# PlaybackStylophone.net
KiCad netlist of a schematic drawn in EAGLE
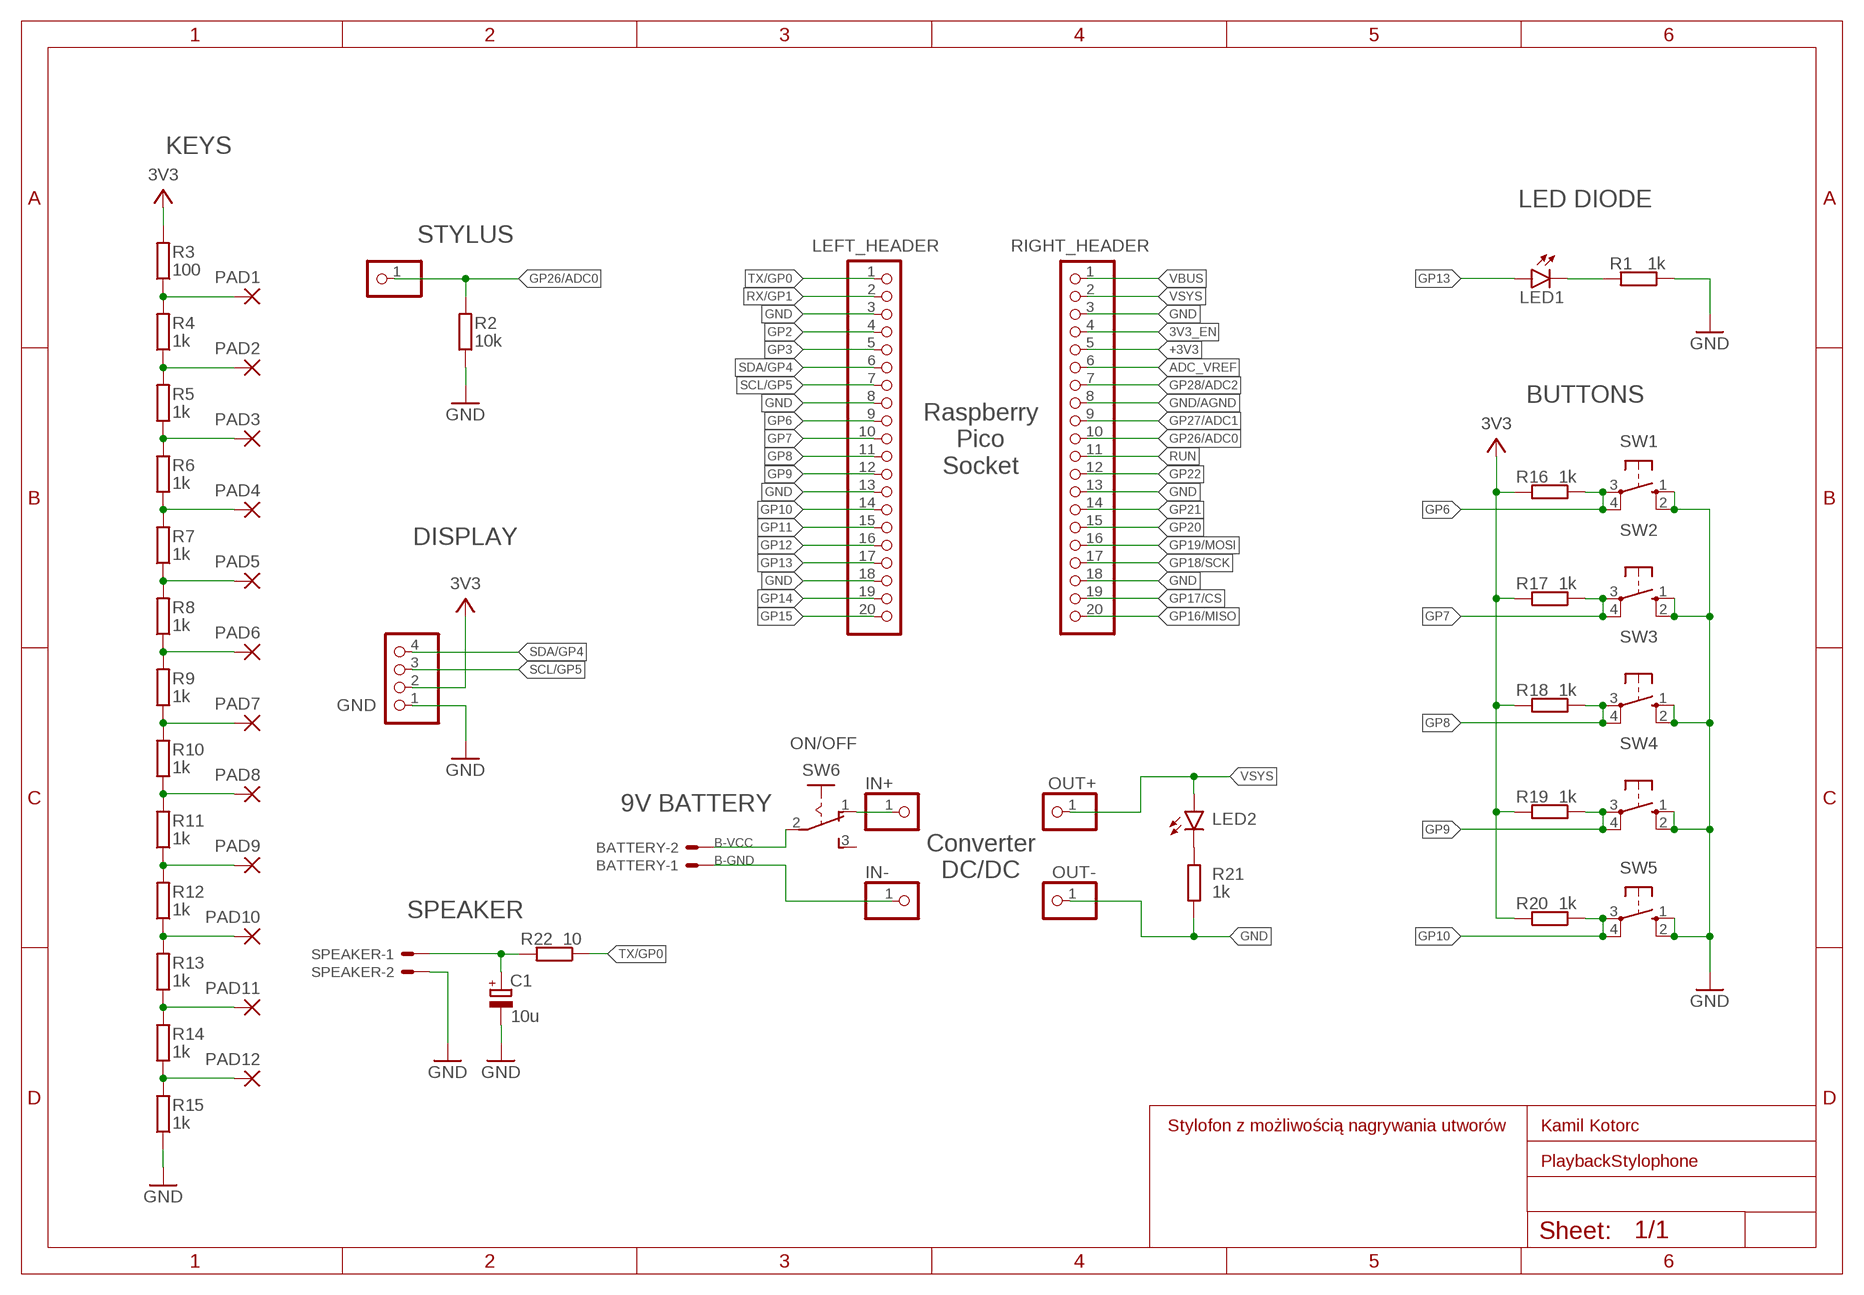
[diagram p0: schematic, sheet 1]

(export (version "E")
  (design (tool "Eeschema 10.0.6"))
  (components
    (comp (ref "BATTERY")
      (value "9V BATTERY")
      (footprint "eagle-import:22-23-2021")
      (fields (field (name "MF") "MOLEX") (field (name "MPN") "22-23-2021"))
      (libsource (lib "eagle-import") (part "22-23-2021"))
    )
    (comp (ref "C1")
      (value "10u")
      (footprint "eagle-import:E2,5-5")
      (libsource (lib "eagle-import") (part "CPOL-EUE2.5-5"))
    )
    (comp (ref "DISPLAY")
      (value "GND")
      (footprint "eagle-import:1X04")
      (libsource (lib "eagle-import") (part "PINHD-1X4"))
    )
    (comp (ref "IN+")
      (value "PINHD-1X1")
      (footprint "eagle-import:1X01")
      (libsource (lib "eagle-import") (part "PINHD-1X1"))
    )
    (comp (ref "IN-")
      (value "PINHD-1X1")
      (footprint "eagle-import:1X01")
      (libsource (lib "eagle-import") (part "PINHD-1X1"))
    )
    (comp (ref "LED1")
      (value "LED5MM")
      (footprint "eagle-import:LED5MM")
      (libsource (lib "eagle-import") (part "LED5MM"))
    )
    (comp (ref "LED2")
      (value "LED3MM")
      (footprint "eagle-import:LED3MM")
      (libsource (lib "eagle-import") (part "LED3MM"))
    )
    (comp (ref "LEFT_HEADER")
      (value "PINHD-1X20")
      (footprint "eagle-import:1X20")
      (libsource (lib "eagle-import") (part "PINHD-1X20"))
    )
    (comp (ref "OUT+")
      (value "PINHD-1X1")
      (footprint "eagle-import:1X01")
      (libsource (lib "eagle-import") (part "PINHD-1X1"))
    )
    (comp (ref "OUT-")
      (value "PINHD-1X1")
      (footprint "eagle-import:1X01")
      (libsource (lib "eagle-import") (part "PINHD-1X1"))
    )
    (comp (ref "PAD1")
      (value "SMD5")
      (footprint "eagle-import:SMD2,54-5,08")
      (libsource (lib "eagle-import") (part "SMD5"))
    )
    (comp (ref "PAD2")
      (value "SMD5")
      (footprint "eagle-import:SMD2,54-5,08")
      (libsource (lib "eagle-import") (part "SMD5"))
    )
    (comp (ref "PAD3")
      (value "SMD5")
      (footprint "eagle-import:SMD2,54-5,08")
      (libsource (lib "eagle-import") (part "SMD5"))
    )
    (comp (ref "PAD4")
      (value "SMD5")
      (footprint "eagle-import:SMD2,54-5,08")
      (libsource (lib "eagle-import") (part "SMD5"))
    )
    (comp (ref "PAD5")
      (value "SMD5")
      (footprint "eagle-import:SMD2,54-5,08")
      (libsource (lib "eagle-import") (part "SMD5"))
    )
    (comp (ref "PAD6")
      (value "SMD5")
      (footprint "eagle-import:SMD2,54-5,08")
      (libsource (lib "eagle-import") (part "SMD5"))
    )
    (comp (ref "PAD7")
      (value "SMD5")
      (footprint "eagle-import:SMD2,54-5,08")
      (libsource (lib "eagle-import") (part "SMD5"))
    )
    (comp (ref "PAD8")
      (value "SMD5")
      (footprint "eagle-import:SMD2,54-5,08")
      (libsource (lib "eagle-import") (part "SMD5"))
    )
    (comp (ref "PAD9")
      (value "SMD5")
      (footprint "eagle-import:SMD2,54-5,08")
      (libsource (lib "eagle-import") (part "SMD5"))
    )
    (comp (ref "PAD10")
      (value "SMD5")
      (footprint "eagle-import:SMD2,54-5,08")
      (libsource (lib "eagle-import") (part "SMD5"))
    )
    (comp (ref "PAD11")
      (value "SMD5")
      (footprint "eagle-import:SMD2,54-5,08")
      (libsource (lib "eagle-import") (part "SMD5"))
    )
    (comp (ref "PAD12")
      (value "SMD5")
      (footprint "eagle-import:SMD2,54-5,08")
      (libsource (lib "eagle-import") (part "SMD5"))
    )
    (comp (ref "R1")
      (value "1k")
      (footprint "eagle-import:0204_7")
      (libsource (lib "eagle-import") (part "R-EU_0204/7"))
    )
    (comp (ref "R2")
      (value "10k")
      (footprint "eagle-import:0204_7")
      (libsource (lib "eagle-import") (part "R-EU_0204/7"))
    )
    (comp (ref "R3")
      (value "100")
      (footprint "eagle-import:0204_7")
      (libsource (lib "eagle-import") (part "R-EU_0204/7"))
    )
    (comp (ref "R4")
      (value "1k")
      (footprint "eagle-import:0204_7")
      (libsource (lib "eagle-import") (part "R-EU_0204/7"))
    )
    (comp (ref "R5")
      (value "1k")
      (footprint "eagle-import:0204_7")
      (libsource (lib "eagle-import") (part "R-EU_0204/7"))
    )
    (comp (ref "R6")
      (value "1k")
      (footprint "eagle-import:0204_7")
      (libsource (lib "eagle-import") (part "R-EU_0204/7"))
    )
    (comp (ref "R7")
      (value "1k")
      (footprint "eagle-import:0204_7")
      (libsource (lib "eagle-import") (part "R-EU_0204/7"))
    )
    (comp (ref "R8")
      (value "1k")
      (footprint "eagle-import:0204_7")
      (libsource (lib "eagle-import") (part "R-EU_0204/7"))
    )
    (comp (ref "R9")
      (value "1k")
      (footprint "eagle-import:0204_7")
      (libsource (lib "eagle-import") (part "R-EU_0204/7"))
    )
    (comp (ref "R10")
      (value "1k")
      (footprint "eagle-import:0204_7")
      (libsource (lib "eagle-import") (part "R-EU_0204/7"))
    )
    (comp (ref "R11")
      (value "1k")
      (footprint "eagle-import:0204_7")
      (libsource (lib "eagle-import") (part "R-EU_0204/7"))
    )
    (comp (ref "R12")
      (value "1k")
      (footprint "eagle-import:0204_7")
      (libsource (lib "eagle-import") (part "R-EU_0204/7"))
    )
    (comp (ref "R13")
      (value "1k")
      (footprint "eagle-import:0204_7")
      (libsource (lib "eagle-import") (part "R-EU_0204/7"))
    )
    (comp (ref "R14")
      (value "1k")
      (footprint "eagle-import:0204_7")
      (libsource (lib "eagle-import") (part "R-EU_0204/7"))
    )
    (comp (ref "R15")
      (value "1k")
      (footprint "eagle-import:0204_7")
      (libsource (lib "eagle-import") (part "R-EU_0204/7"))
    )
    (comp (ref "R16")
      (value "1k")
      (footprint "eagle-import:0204_7")
      (libsource (lib "eagle-import") (part "R-EU_0204/7"))
    )
    (comp (ref "R17")
      (value "1k")
      (footprint "eagle-import:0204_7")
      (libsource (lib "eagle-import") (part "R-EU_0204/7"))
    )
    (comp (ref "R18")
      (value "1k")
      (footprint "eagle-import:0204_7")
      (libsource (lib "eagle-import") (part "R-EU_0204/7"))
    )
    (comp (ref "R19")
      (value "1k")
      (footprint "eagle-import:0204_7")
      (libsource (lib "eagle-import") (part "R-EU_0204/7"))
    )
    (comp (ref "R20")
      (value "1k")
      (footprint "eagle-import:0204_7")
      (libsource (lib "eagle-import") (part "R-EU_0204/7"))
    )
    (comp (ref "R21")
      (value "1k")
      (footprint "eagle-import:0204_7")
      (libsource (lib "eagle-import") (part "R-EU_0204/7"))
    )
    (comp (ref "R22")
      (value "10")
      (footprint "eagle-import:0204_7")
      (libsource (lib "eagle-import") (part "R-EU_0204/7"))
    )
    (comp (ref "RIGHT_HEADER")
      (value "PINHD-1X20")
      (footprint "eagle-import:1X20")
      (libsource (lib "eagle-import") (part "PINHD-1X20"))
    )
    (comp (ref "SPEAKER")
      (value "SPEAKER")
      (footprint "eagle-import:22-23-2021")
      (fields (field (name "MF") "MOLEX") (field (name "MPN") "22-23-2021"))
      (libsource (lib "eagle-import") (part "22-23-2021"))
    )
    (comp (ref "STYLUS")
      (value "PINHD-1X1")
      (footprint "eagle-import:1X01")
      (libsource (lib "eagle-import") (part "PINHD-1X1"))
    )
    (comp (ref "SW1")
      (value "10-XX")
      (footprint "eagle-import:B3F-10XX")
      (fields (field (name "MPN") "B3F-1000"))
      (libsource (lib "eagle-import") (part "10-XX"))
    )
    (comp (ref "SW2")
      (value "10-XX")
      (footprint "eagle-import:B3F-10XX")
      (fields (field (name "MPN") "B3F-1000"))
      (libsource (lib "eagle-import") (part "10-XX"))
    )
    (comp (ref "SW3")
      (value "10-XX")
      (footprint "eagle-import:B3F-10XX")
      (fields (field (name "MPN") "B3F-1000"))
      (libsource (lib "eagle-import") (part "10-XX"))
    )
    (comp (ref "SW4")
      (value "10-XX")
      (footprint "eagle-import:B3F-10XX")
      (fields (field (name "MPN") "B3F-1000"))
      (libsource (lib "eagle-import") (part "10-XX"))
    )
    (comp (ref "SW5")
      (value "10-XX")
      (footprint "eagle-import:B3F-10XX")
      (fields (field (name "MPN") "B3F-1000"))
      (libsource (lib "eagle-import") (part "10-XX"))
    )
    (comp (ref "SW6")
      (value "ON/OFF")
      (footprint "eagle-import:255SB")
      (libsource (lib "eagle-import") (part "255SB"))
    )
  )
  (nets
    (net (code "1") (name "+3V3") (class "Default")
      (node (ref "DISPLAY") (pin "2") (pinfunction "2_2") (pintype "passive"))
      (node (ref "R16") (pin "2") (pinfunction "2_2") (pintype "passive"))
      (node (ref "R17") (pin "2") (pinfunction "2_2") (pintype "passive"))
      (node (ref "R18") (pin "2") (pinfunction "2_2") (pintype "passive"))
      (node (ref "R19") (pin "2") (pinfunction "2_2") (pintype "passive"))
      (node (ref "R20") (pin "2") (pinfunction "2_2") (pintype "passive"))
      (node (ref "R3") (pin "2") (pinfunction "2_2") (pintype "passive"))
      (node (ref "RIGHT_HEADER") (pin "5") (pinfunction "5_5") (pintype "passive"))
    )
    (net (code "2") (name "/B-GND") (class "Default")
      (node (ref "BATTERY") (pin "1") (pinfunction "S_1") (pintype "passive"))
      (node (ref "IN-") (pin "1") (pinfunction "1_1") (pintype "passive"))
    )
    (net (code "3") (name "/B-VCC") (class "Default")
      (node (ref "BATTERY") (pin "2") (pinfunction "S_2") (pintype "passive"))
      (node (ref "SW6") (pin "2") (pinfunction "P_2") (pintype "passive"))
    )
    (net (code "4") (name "3V3_EN") (class "Default")
      (node (ref "RIGHT_HEADER") (pin "4") (pinfunction "4_4") (pintype "passive"))
    )
    (net (code "5") (name "ADC_VREF") (class "Default")
      (node (ref "RIGHT_HEADER") (pin "6") (pinfunction "6_6") (pintype "passive"))
    )
    (net (code "6") (name "GND") (class "Default")
      (node (ref "C1") (pin "-") (pinfunction "-_-") (pintype "passive"))
      (node (ref "DISPLAY") (pin "1") (pinfunction "1_1") (pintype "passive"))
      (node (ref "LEFT_HEADER") (pin "13") (pinfunction "13_13") (pintype "passive"))
      (node (ref "LEFT_HEADER") (pin "18") (pinfunction "18_18") (pintype "passive"))
      (node (ref "LEFT_HEADER") (pin "3") (pinfunction "3_3") (pintype "passive"))
      (node (ref "LEFT_HEADER") (pin "8") (pinfunction "8_8") (pintype "passive"))
      (node (ref "OUT-") (pin "1") (pinfunction "1_1") (pintype "passive"))
      (node (ref "R1") (pin "1") (pinfunction "1_1") (pintype "passive"))
      (node (ref "R15") (pin "1") (pinfunction "1_1") (pintype "passive"))
      (node (ref "R2") (pin "1") (pinfunction "1_1") (pintype "passive"))
      (node (ref "R21") (pin "1") (pinfunction "1_1") (pintype "passive"))
      (node (ref "RIGHT_HEADER") (pin "13") (pinfunction "13_13") (pintype "passive"))
      (node (ref "RIGHT_HEADER") (pin "18") (pinfunction "18_18") (pintype "passive"))
      (node (ref "RIGHT_HEADER") (pin "3") (pinfunction "3_3") (pintype "passive"))
      (node (ref "SPEAKER") (pin "2") (pinfunction "S_2") (pintype "passive"))
      (node (ref "SW1") (pin "1") (pinfunction "S_1") (pintype "passive"))
      (node (ref "SW1") (pin "2") (pinfunction "S1_2") (pintype "passive"))
      (node (ref "SW2") (pin "1") (pinfunction "S_1") (pintype "passive"))
      (node (ref "SW2") (pin "2") (pinfunction "S1_2") (pintype "passive"))
      (node (ref "SW3") (pin "1") (pinfunction "S_1") (pintype "passive"))
      (node (ref "SW3") (pin "2") (pinfunction "S1_2") (pintype "passive"))
      (node (ref "SW4") (pin "1") (pinfunction "S_1") (pintype "passive"))
      (node (ref "SW4") (pin "2") (pinfunction "S1_2") (pintype "passive"))
      (node (ref "SW5") (pin "1") (pinfunction "S_1") (pintype "passive"))
      (node (ref "SW5") (pin "2") (pinfunction "S1_2") (pintype "passive"))
    )
    (net (code "7") (name "GND{slash}AGND") (class "Default")
      (node (ref "RIGHT_HEADER") (pin "8") (pinfunction "8_8") (pintype "passive"))
    )
    (net (code "8") (name "GP2") (class "Default")
      (node (ref "LEFT_HEADER") (pin "4") (pinfunction "4_4") (pintype "passive"))
    )
    (net (code "9") (name "GP3") (class "Default")
      (node (ref "LEFT_HEADER") (pin "5") (pinfunction "5_5") (pintype "passive"))
    )
    (net (code "10") (name "GP6") (class "Default")
      (node (ref "LEFT_HEADER") (pin "9") (pinfunction "9_9") (pintype "passive"))
      (node (ref "R16") (pin "1") (pinfunction "1_1") (pintype "passive"))
      (node (ref "SW1") (pin "3") (pinfunction "P_3") (pintype "passive"))
      (node (ref "SW1") (pin "4") (pinfunction "P1_4") (pintype "passive"))
    )
    (net (code "11") (name "GP7") (class "Default")
      (node (ref "LEFT_HEADER") (pin "10") (pinfunction "10_10") (pintype "passive"))
      (node (ref "R17") (pin "1") (pinfunction "1_1") (pintype "passive"))
      (node (ref "SW2") (pin "3") (pinfunction "P_3") (pintype "passive"))
      (node (ref "SW2") (pin "4") (pinfunction "P1_4") (pintype "passive"))
    )
    (net (code "12") (name "GP8") (class "Default")
      (node (ref "LEFT_HEADER") (pin "11") (pinfunction "11_11") (pintype "passive"))
      (node (ref "R18") (pin "1") (pinfunction "1_1") (pintype "passive"))
      (node (ref "SW3") (pin "3") (pinfunction "P_3") (pintype "passive"))
      (node (ref "SW3") (pin "4") (pinfunction "P1_4") (pintype "passive"))
    )
    (net (code "13") (name "GP9") (class "Default")
      (node (ref "LEFT_HEADER") (pin "12") (pinfunction "12_12") (pintype "passive"))
      (node (ref "R19") (pin "1") (pinfunction "1_1") (pintype "passive"))
      (node (ref "SW4") (pin "3") (pinfunction "P_3") (pintype "passive"))
      (node (ref "SW4") (pin "4") (pinfunction "P1_4") (pintype "passive"))
    )
    (net (code "14") (name "GP10") (class "Default")
      (node (ref "LEFT_HEADER") (pin "14") (pinfunction "14_14") (pintype "passive"))
      (node (ref "R20") (pin "1") (pinfunction "1_1") (pintype "passive"))
      (node (ref "SW5") (pin "3") (pinfunction "P_3") (pintype "passive"))
      (node (ref "SW5") (pin "4") (pinfunction "P1_4") (pintype "passive"))
    )
    (net (code "15") (name "GP11") (class "Default")
      (node (ref "LEFT_HEADER") (pin "15") (pinfunction "15_15") (pintype "passive"))
    )
    (net (code "16") (name "GP12") (class "Default")
      (node (ref "LEFT_HEADER") (pin "16") (pinfunction "16_16") (pintype "passive"))
    )
    (net (code "17") (name "GP13") (class "Default")
      (node (ref "LED1") (pin "A") (pinfunction "A_A") (pintype "passive"))
      (node (ref "LEFT_HEADER") (pin "17") (pinfunction "17_17") (pintype "passive"))
    )
    (net (code "18") (name "GP14") (class "Default")
      (node (ref "LEFT_HEADER") (pin "19") (pinfunction "19_19") (pintype "passive"))
    )
    (net (code "19") (name "GP15") (class "Default")
      (node (ref "LEFT_HEADER") (pin "20") (pinfunction "20_20") (pintype "passive"))
    )
    (net (code "20") (name "GP16{slash}MISO") (class "Default")
      (node (ref "RIGHT_HEADER") (pin "20") (pinfunction "20_20") (pintype "passive"))
    )
    (net (code "21") (name "GP17{slash}CS") (class "Default")
      (node (ref "RIGHT_HEADER") (pin "19") (pinfunction "19_19") (pintype "passive"))
    )
    (net (code "22") (name "GP18{slash}SCK") (class "Default")
      (node (ref "RIGHT_HEADER") (pin "17") (pinfunction "17_17") (pintype "passive"))
    )
    (net (code "23") (name "GP19{slash}MOSI") (class "Default")
      (node (ref "RIGHT_HEADER") (pin "16") (pinfunction "16_16") (pintype "passive"))
    )
    (net (code "24") (name "GP20") (class "Default")
      (node (ref "RIGHT_HEADER") (pin "15") (pinfunction "15_15") (pintype "passive"))
    )
    (net (code "25") (name "GP21") (class "Default")
      (node (ref "RIGHT_HEADER") (pin "14") (pinfunction "14_14") (pintype "passive"))
    )
    (net (code "26") (name "GP22") (class "Default")
      (node (ref "RIGHT_HEADER") (pin "12") (pinfunction "12_12") (pintype "passive"))
    )
    (net (code "27") (name "GP26{slash}ADC0") (class "Default")
      (node (ref "R2") (pin "2") (pinfunction "2_2") (pintype "passive"))
      (node (ref "RIGHT_HEADER") (pin "10") (pinfunction "10_10") (pintype "passive"))
      (node (ref "STYLUS") (pin "1") (pinfunction "1_1") (pintype "passive"))
    )
    (net (code "28") (name "GP27{slash}ADC1") (class "Default")
      (node (ref "RIGHT_HEADER") (pin "9") (pinfunction "9_9") (pintype "passive"))
    )
    (net (code "29") (name "GP28{slash}ADC2") (class "Default")
      (node (ref "RIGHT_HEADER") (pin "7") (pinfunction "7_7") (pintype "passive"))
    )
    (net (code "30") (name "Net-(LED1-C)") (class "Default")
      (node (ref "LED1") (pin "K") (pinfunction "C_K") (pintype "passive"))
      (node (ref "R1") (pin "2") (pinfunction "2_2") (pintype "passive"))
    )
    (net (code "31") (name "Net-(LED2-C)") (class "Default")
      (node (ref "LED2") (pin "K") (pinfunction "C_K") (pintype "passive"))
      (node (ref "R21") (pin "2") (pinfunction "2_2") (pintype "passive"))
    )
    (net (code "32") (name "Net-(PAD1-P)") (class "Default")
      (node (ref "PAD1") (pin "1") (pinfunction "P_1") (pintype "passive"))
      (node (ref "R3") (pin "1") (pinfunction "1_1") (pintype "passive"))
      (node (ref "R4") (pin "2") (pinfunction "2_2") (pintype "passive"))
    )
    (net (code "33") (name "Net-(PAD2-P)") (class "Default")
      (node (ref "PAD2") (pin "1") (pinfunction "P_1") (pintype "passive"))
      (node (ref "R4") (pin "1") (pinfunction "1_1") (pintype "passive"))
      (node (ref "R5") (pin "2") (pinfunction "2_2") (pintype "passive"))
    )
    (net (code "34") (name "Net-(PAD3-P)") (class "Default")
      (node (ref "PAD3") (pin "1") (pinfunction "P_1") (pintype "passive"))
      (node (ref "R5") (pin "1") (pinfunction "1_1") (pintype "passive"))
      (node (ref "R6") (pin "2") (pinfunction "2_2") (pintype "passive"))
    )
    (net (code "35") (name "Net-(PAD4-P)") (class "Default")
      (node (ref "PAD4") (pin "1") (pinfunction "P_1") (pintype "passive"))
      (node (ref "R6") (pin "1") (pinfunction "1_1") (pintype "passive"))
      (node (ref "R7") (pin "2") (pinfunction "2_2") (pintype "passive"))
    )
    (net (code "36") (name "Net-(PAD5-P)") (class "Default")
      (node (ref "PAD5") (pin "1") (pinfunction "P_1") (pintype "passive"))
      (node (ref "R7") (pin "1") (pinfunction "1_1") (pintype "passive"))
      (node (ref "R8") (pin "2") (pinfunction "2_2") (pintype "passive"))
    )
    (net (code "37") (name "Net-(PAD6-P)") (class "Default")
      (node (ref "PAD6") (pin "1") (pinfunction "P_1") (pintype "passive"))
      (node (ref "R8") (pin "1") (pinfunction "1_1") (pintype "passive"))
      (node (ref "R9") (pin "2") (pinfunction "2_2") (pintype "passive"))
    )
    (net (code "38") (name "Net-(PAD7-P)") (class "Default")
      (node (ref "PAD7") (pin "1") (pinfunction "P_1") (pintype "passive"))
      (node (ref "R10") (pin "2") (pinfunction "2_2") (pintype "passive"))
      (node (ref "R9") (pin "1") (pinfunction "1_1") (pintype "passive"))
    )
    (net (code "39") (name "Net-(PAD8-P)") (class "Default")
      (node (ref "PAD8") (pin "1") (pinfunction "P_1") (pintype "passive"))
      (node (ref "R10") (pin "1") (pinfunction "1_1") (pintype "passive"))
      (node (ref "R11") (pin "2") (pinfunction "2_2") (pintype "passive"))
    )
    (net (code "40") (name "Net-(PAD9-P)") (class "Default")
      (node (ref "PAD9") (pin "1") (pinfunction "P_1") (pintype "passive"))
      (node (ref "R11") (pin "1") (pinfunction "1_1") (pintype "passive"))
      (node (ref "R12") (pin "2") (pinfunction "2_2") (pintype "passive"))
    )
    (net (code "41") (name "Net-(PAD10-P)") (class "Default")
      (node (ref "PAD10") (pin "1") (pinfunction "P_1") (pintype "passive"))
      (node (ref "R12") (pin "1") (pinfunction "1_1") (pintype "passive"))
      (node (ref "R13") (pin "2") (pinfunction "2_2") (pintype "passive"))
    )
    (net (code "42") (name "Net-(PAD11-P)") (class "Default")
      (node (ref "PAD11") (pin "1") (pinfunction "P_1") (pintype "passive"))
      (node (ref "R13") (pin "1") (pinfunction "1_1") (pintype "passive"))
      (node (ref "R14") (pin "2") (pinfunction "2_2") (pintype "passive"))
    )
    (net (code "43") (name "Net-(PAD12-P)") (class "Default")
      (node (ref "PAD12") (pin "1") (pinfunction "P_1") (pintype "passive"))
      (node (ref "R14") (pin "1") (pinfunction "1_1") (pintype "passive"))
      (node (ref "R15") (pin "2") (pinfunction "2_2") (pintype "passive"))
    )
    (net (code "44") (name "Net-(SPEAKERA-S)") (class "Default")
      (node (ref "C1") (pin "+") (pinfunction "+_+") (pintype "passive"))
      (node (ref "R22") (pin "2") (pinfunction "2_2") (pintype "passive"))
      (node (ref "SPEAKER") (pin "1") (pinfunction "S_1") (pintype "passive"))
    )
    (net (code "45") (name "Net-(SW6-O)") (class "Default")
      (node (ref "IN+") (pin "1") (pinfunction "1_1") (pintype "passive"))
      (node (ref "SW6") (pin "1") (pinfunction "O_1") (pintype "passive"))
    )
    (net (code "46") (name "RUN") (class "Default")
      (node (ref "RIGHT_HEADER") (pin "11") (pinfunction "11_11") (pintype "passive"))
    )
    (net (code "47") (name "RX{slash}GP1") (class "Default")
      (node (ref "LEFT_HEADER") (pin "2") (pinfunction "2_2") (pintype "passive"))
    )
    (net (code "48") (name "SCL{slash}GP5") (class "Default")
      (node (ref "DISPLAY") (pin "3") (pinfunction "3_3") (pintype "passive"))
      (node (ref "LEFT_HEADER") (pin "7") (pinfunction "7_7") (pintype "passive"))
    )
    (net (code "49") (name "SDA{slash}GP4") (class "Default")
      (node (ref "DISPLAY") (pin "4") (pinfunction "4_4") (pintype "passive"))
      (node (ref "LEFT_HEADER") (pin "6") (pinfunction "6_6") (pintype "passive"))
    )
    (net (code "50") (name "TX{slash}GP0") (class "Default")
      (node (ref "LEFT_HEADER") (pin "1") (pinfunction "1_1") (pintype "passive"))
      (node (ref "R22") (pin "1") (pinfunction "1_1") (pintype "passive"))
    )
    (net (code "51") (name "VBUS") (class "Default")
      (node (ref "RIGHT_HEADER") (pin "1") (pinfunction "1_1") (pintype "passive"))
    )
    (net (code "52") (name "VSYS") (class "Default")
      (node (ref "LED2") (pin "A") (pinfunction "A_A") (pintype "passive"))
      (node (ref "OUT+") (pin "1") (pinfunction "1_1") (pintype "passive"))
      (node (ref "RIGHT_HEADER") (pin "2") (pinfunction "2_2") (pintype "passive"))
    )
    (net (code "53") (name "unconnected-(SW6-S-Pad3)") (class "Default")
      (node (ref "SW6") (pin "3") (pinfunction "S_3") (pintype "passive"))
    )
  )
)
